# lp_breadboard.net
KiCad netlist of a schematic drawn in EAGLE
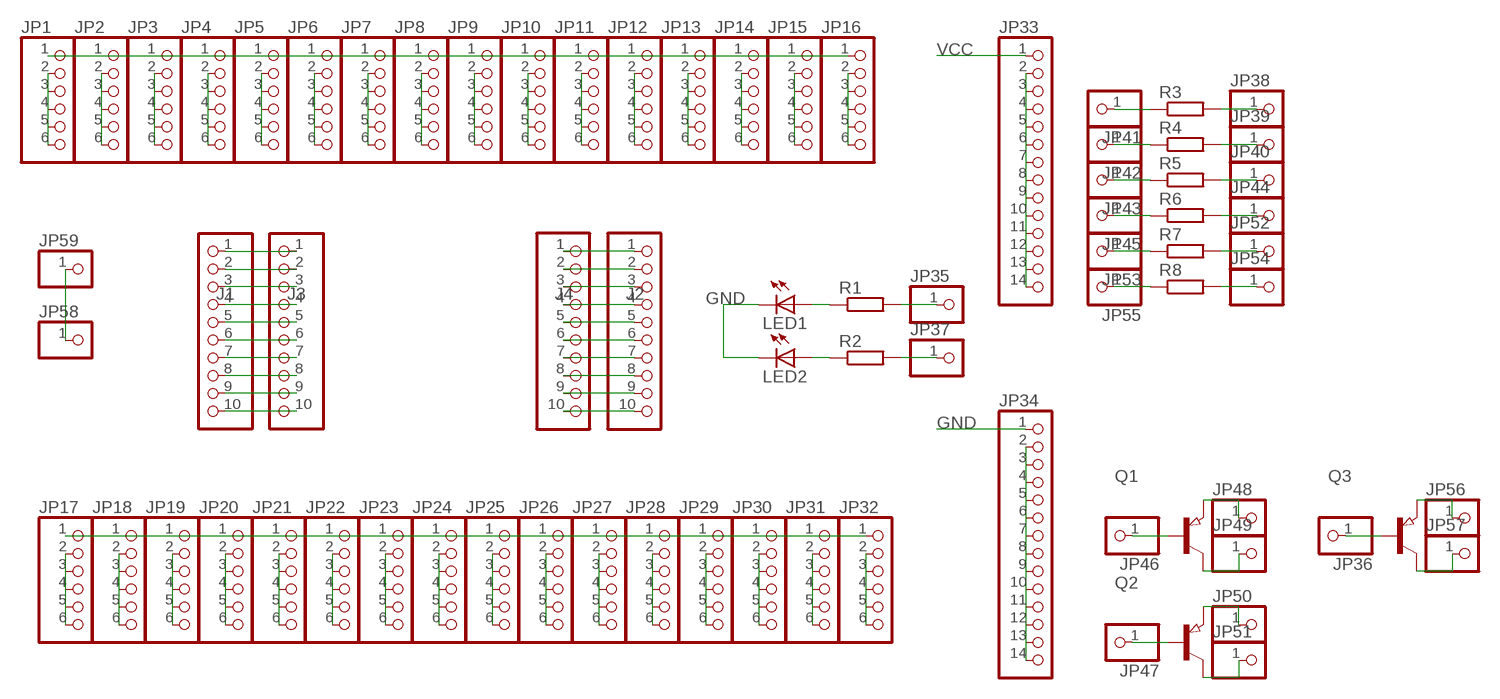
[diagram p0: schematic, sheet 1]

(export (version "E")
  (design (tool "Eeschema 10.0.6"))
  (components
    (comp (ref "J1")
      (value "PINHD-1X10")
      (footprint "eagle-import:1X10")
      (libsource (lib "eagle-import") (part "PINHD-1X10"))
    )
    (comp (ref "J2")
      (value "PINHD-1X10")
      (footprint "eagle-import:1X10")
      (libsource (lib "eagle-import") (part "PINHD-1X10"))
    )
    (comp (ref "J3")
      (value "PINHD-1X10")
      (footprint "eagle-import:1X10")
      (libsource (lib "eagle-import") (part "PINHD-1X10"))
    )
    (comp (ref "J4")
      (value "PINHD-1X10")
      (footprint "eagle-import:1X10")
      (libsource (lib "eagle-import") (part "PINHD-1X10"))
    )
    (comp (ref "JP1")
      (value "PINHD-1X6")
      (footprint "eagle-import:1X06")
      (libsource (lib "eagle-import") (part "PINHD-1X6"))
    )
    (comp (ref "JP2")
      (value "PINHD-1X6")
      (footprint "eagle-import:1X06")
      (libsource (lib "eagle-import") (part "PINHD-1X6"))
    )
    (comp (ref "JP3")
      (value "PINHD-1X6")
      (footprint "eagle-import:1X06")
      (libsource (lib "eagle-import") (part "PINHD-1X6"))
    )
    (comp (ref "JP4")
      (value "PINHD-1X6")
      (footprint "eagle-import:1X06")
      (libsource (lib "eagle-import") (part "PINHD-1X6"))
    )
    (comp (ref "JP5")
      (value "PINHD-1X6")
      (footprint "eagle-import:1X06")
      (libsource (lib "eagle-import") (part "PINHD-1X6"))
    )
    (comp (ref "JP6")
      (value "PINHD-1X6")
      (footprint "eagle-import:1X06")
      (libsource (lib "eagle-import") (part "PINHD-1X6"))
    )
    (comp (ref "JP7")
      (value "PINHD-1X6")
      (footprint "eagle-import:1X06")
      (libsource (lib "eagle-import") (part "PINHD-1X6"))
    )
    (comp (ref "JP8")
      (value "PINHD-1X6")
      (footprint "eagle-import:1X06")
      (libsource (lib "eagle-import") (part "PINHD-1X6"))
    )
    (comp (ref "JP9")
      (value "PINHD-1X6")
      (footprint "eagle-import:1X06")
      (libsource (lib "eagle-import") (part "PINHD-1X6"))
    )
    (comp (ref "JP10")
      (value "PINHD-1X6")
      (footprint "eagle-import:1X06")
      (libsource (lib "eagle-import") (part "PINHD-1X6"))
    )
    (comp (ref "JP11")
      (value "PINHD-1X6")
      (footprint "eagle-import:1X06")
      (libsource (lib "eagle-import") (part "PINHD-1X6"))
    )
    (comp (ref "JP12")
      (value "PINHD-1X6")
      (footprint "eagle-import:1X06")
      (libsource (lib "eagle-import") (part "PINHD-1X6"))
    )
    (comp (ref "JP13")
      (value "PINHD-1X6")
      (footprint "eagle-import:1X06")
      (libsource (lib "eagle-import") (part "PINHD-1X6"))
    )
    (comp (ref "JP14")
      (value "PINHD-1X6")
      (footprint "eagle-import:1X06")
      (libsource (lib "eagle-import") (part "PINHD-1X6"))
    )
    (comp (ref "JP15")
      (value "PINHD-1X6")
      (footprint "eagle-import:1X06")
      (libsource (lib "eagle-import") (part "PINHD-1X6"))
    )
    (comp (ref "JP16")
      (value "PINHD-1X6")
      (footprint "eagle-import:1X06")
      (libsource (lib "eagle-import") (part "PINHD-1X6"))
    )
    (comp (ref "JP17")
      (value "PINHD-1X6")
      (footprint "eagle-import:1X06")
      (libsource (lib "eagle-import") (part "PINHD-1X6"))
    )
    (comp (ref "JP18")
      (value "PINHD-1X6")
      (footprint "eagle-import:1X06")
      (libsource (lib "eagle-import") (part "PINHD-1X6"))
    )
    (comp (ref "JP19")
      (value "PINHD-1X6")
      (footprint "eagle-import:1X06")
      (libsource (lib "eagle-import") (part "PINHD-1X6"))
    )
    (comp (ref "JP20")
      (value "PINHD-1X6")
      (footprint "eagle-import:1X06")
      (libsource (lib "eagle-import") (part "PINHD-1X6"))
    )
    (comp (ref "JP21")
      (value "PINHD-1X6")
      (footprint "eagle-import:1X06")
      (libsource (lib "eagle-import") (part "PINHD-1X6"))
    )
    (comp (ref "JP22")
      (value "PINHD-1X6")
      (footprint "eagle-import:1X06")
      (libsource (lib "eagle-import") (part "PINHD-1X6"))
    )
    (comp (ref "JP23")
      (value "PINHD-1X6")
      (footprint "eagle-import:1X06")
      (libsource (lib "eagle-import") (part "PINHD-1X6"))
    )
    (comp (ref "JP24")
      (value "PINHD-1X6")
      (footprint "eagle-import:1X06")
      (libsource (lib "eagle-import") (part "PINHD-1X6"))
    )
    (comp (ref "JP25")
      (value "PINHD-1X6")
      (footprint "eagle-import:1X06")
      (libsource (lib "eagle-import") (part "PINHD-1X6"))
    )
    (comp (ref "JP26")
      (value "PINHD-1X6")
      (footprint "eagle-import:1X06")
      (libsource (lib "eagle-import") (part "PINHD-1X6"))
    )
    (comp (ref "JP27")
      (value "PINHD-1X6")
      (footprint "eagle-import:1X06")
      (libsource (lib "eagle-import") (part "PINHD-1X6"))
    )
    (comp (ref "JP28")
      (value "PINHD-1X6")
      (footprint "eagle-import:1X06")
      (libsource (lib "eagle-import") (part "PINHD-1X6"))
    )
    (comp (ref "JP29")
      (value "PINHD-1X6")
      (footprint "eagle-import:1X06")
      (libsource (lib "eagle-import") (part "PINHD-1X6"))
    )
    (comp (ref "JP30")
      (value "PINHD-1X6")
      (footprint "eagle-import:1X06")
      (libsource (lib "eagle-import") (part "PINHD-1X6"))
    )
    (comp (ref "JP31")
      (value "PINHD-1X6")
      (footprint "eagle-import:1X06")
      (libsource (lib "eagle-import") (part "PINHD-1X6"))
    )
    (comp (ref "JP32")
      (value "PINHD-1X6")
      (footprint "eagle-import:1X06")
      (libsource (lib "eagle-import") (part "PINHD-1X6"))
    )
    (comp (ref "JP33")
      (value "PINHD-1X14")
      (footprint "eagle-import:1X14")
      (libsource (lib "eagle-import") (part "PINHD-1X14"))
    )
    (comp (ref "JP34")
      (value "PINHD-1X14")
      (footprint "eagle-import:1X14")
      (libsource (lib "eagle-import") (part "PINHD-1X14"))
    )
    (comp (ref "JP35")
      (value "PINHD-1X1")
      (footprint "eagle-import:1X01")
      (libsource (lib "eagle-import") (part "PINHD-1X1"))
    )
    (comp (ref "JP36")
      (value "PINHD-1X1")
      (footprint "eagle-import:1X01")
      (libsource (lib "eagle-import") (part "PINHD-1X1"))
    )
    (comp (ref "JP37")
      (value "PINHD-1X1")
      (footprint "eagle-import:1X01")
      (libsource (lib "eagle-import") (part "PINHD-1X1"))
    )
    (comp (ref "JP38")
      (value "PINHD-1X1")
      (footprint "eagle-import:1X01")
      (libsource (lib "eagle-import") (part "PINHD-1X1"))
    )
    (comp (ref "JP39")
      (value "PINHD-1X1")
      (footprint "eagle-import:1X01")
      (libsource (lib "eagle-import") (part "PINHD-1X1"))
    )
    (comp (ref "JP40")
      (value "PINHD-1X1")
      (footprint "eagle-import:1X01")
      (libsource (lib "eagle-import") (part "PINHD-1X1"))
    )
    (comp (ref "JP41")
      (value "PINHD-1X1")
      (footprint "eagle-import:1X01")
      (libsource (lib "eagle-import") (part "PINHD-1X1"))
    )
    (comp (ref "JP42")
      (value "PINHD-1X1")
      (footprint "eagle-import:1X01")
      (libsource (lib "eagle-import") (part "PINHD-1X1"))
    )
    (comp (ref "JP43")
      (value "PINHD-1X1")
      (footprint "eagle-import:1X01")
      (libsource (lib "eagle-import") (part "PINHD-1X1"))
    )
    (comp (ref "JP44")
      (value "PINHD-1X1")
      (footprint "eagle-import:1X01")
      (libsource (lib "eagle-import") (part "PINHD-1X1"))
    )
    (comp (ref "JP45")
      (value "PINHD-1X1")
      (footprint "eagle-import:1X01")
      (libsource (lib "eagle-import") (part "PINHD-1X1"))
    )
    (comp (ref "JP46")
      (value "PINHD-1X1")
      (footprint "eagle-import:1X01")
      (libsource (lib "eagle-import") (part "PINHD-1X1"))
    )
    (comp (ref "JP47")
      (value "PINHD-1X1")
      (footprint "eagle-import:1X01")
      (libsource (lib "eagle-import") (part "PINHD-1X1"))
    )
    (comp (ref "JP48")
      (value "PINHD-1X1")
      (footprint "eagle-import:1X01")
      (libsource (lib "eagle-import") (part "PINHD-1X1"))
    )
    (comp (ref "JP49")
      (value "PINHD-1X1")
      (footprint "eagle-import:1X01")
      (libsource (lib "eagle-import") (part "PINHD-1X1"))
    )
    (comp (ref "JP50")
      (value "PINHD-1X1")
      (footprint "eagle-import:1X01")
      (libsource (lib "eagle-import") (part "PINHD-1X1"))
    )
    (comp (ref "JP51")
      (value "PINHD-1X1")
      (footprint "eagle-import:1X01")
      (libsource (lib "eagle-import") (part "PINHD-1X1"))
    )
    (comp (ref "JP52")
      (value "PINHD-1X1")
      (footprint "eagle-import:1X01")
      (libsource (lib "eagle-import") (part "PINHD-1X1"))
    )
    (comp (ref "JP53")
      (value "PINHD-1X1")
      (footprint "eagle-import:1X01")
      (libsource (lib "eagle-import") (part "PINHD-1X1"))
    )
    (comp (ref "JP54")
      (value "PINHD-1X1")
      (footprint "eagle-import:1X01")
      (libsource (lib "eagle-import") (part "PINHD-1X1"))
    )
    (comp (ref "JP55")
      (value "PINHD-1X1")
      (footprint "eagle-import:1X01")
      (libsource (lib "eagle-import") (part "PINHD-1X1"))
    )
    (comp (ref "JP56")
      (value "PINHD-1X1")
      (footprint "eagle-import:1X01")
      (libsource (lib "eagle-import") (part "PINHD-1X1"))
    )
    (comp (ref "JP57")
      (value "PINHD-1X1")
      (footprint "eagle-import:1X01")
      (libsource (lib "eagle-import") (part "PINHD-1X1"))
    )
    (comp (ref "JP58")
      (value "PINHD-1X1")
      (footprint "eagle-import:1X01")
      (libsource (lib "eagle-import") (part "PINHD-1X1"))
    )
    (comp (ref "JP59")
      (value "PINHD-1X1")
      (footprint "eagle-import:1X01")
      (libsource (lib "eagle-import") (part "PINHD-1X1"))
    )
    (comp (ref "LED1")
      (value "LEDCHIPLED_1206")
      (footprint "eagle-import:CHIPLED_1206")
      (libsource (lib "eagle-import") (part "LEDCHIPLED_1206"))
    )
    (comp (ref "LED2")
      (value "LEDCHIPLED_1206")
      (footprint "eagle-import:CHIPLED_1206")
      (libsource (lib "eagle-import") (part "LEDCHIPLED_1206"))
    )
    (comp (ref "Q1")
      (value "PNP-TRANSISTOR_SOT23")
      (footprint "eagle-import:SOT23")
      (libsource (lib "eagle-import") (part "PNP-TRANSISTOR_SOT23"))
    )
    (comp (ref "Q2")
      (value "PNP-TRANSISTOR_SOT23")
      (footprint "eagle-import:SOT23")
      (libsource (lib "eagle-import") (part "PNP-TRANSISTOR_SOT23"))
    )
    (comp (ref "Q3")
      (value "PNP-TRANSISTOR_SOT23")
      (footprint "eagle-import:SOT23")
      (libsource (lib "eagle-import") (part "PNP-TRANSISTOR_SOT23"))
    )
    (comp (ref "R1")
      (value "R-EU_R0805")
      (footprint "eagle-import:R0805")
      (libsource (lib "eagle-import") (part "R-EU_R0805"))
    )
    (comp (ref "R2")
      (value "R-EU_R0805")
      (footprint "eagle-import:R0805")
      (libsource (lib "eagle-import") (part "R-EU_R0805"))
    )
    (comp (ref "R3")
      (value "R-EU_R0805")
      (footprint "eagle-import:R0805")
      (libsource (lib "eagle-import") (part "R-EU_R0805"))
    )
    (comp (ref "R4")
      (value "R-EU_R0805")
      (footprint "eagle-import:R0805")
      (libsource (lib "eagle-import") (part "R-EU_R0805"))
    )
    (comp (ref "R5")
      (value "R-EU_R0805")
      (footprint "eagle-import:R0805")
      (libsource (lib "eagle-import") (part "R-EU_R0805"))
    )
    (comp (ref "R6")
      (value "R-EU_R0805")
      (footprint "eagle-import:R0805")
      (libsource (lib "eagle-import") (part "R-EU_R0805"))
    )
    (comp (ref "R7")
      (value "R-EU_R0805")
      (footprint "eagle-import:R0805")
      (libsource (lib "eagle-import") (part "R-EU_R0805"))
    )
    (comp (ref "R8")
      (value "R-EU_R0805")
      (footprint "eagle-import:R0805")
      (libsource (lib "eagle-import") (part "R-EU_R0805"))
    )
  )
  (nets
    (net (code "1") (name "/GND") (class "Default")
      (node (ref "J2") (pin "1") (pinfunction "1_1") (pintype "passive"))
      (node (ref "J4") (pin "1") (pinfunction "1_1") (pintype "passive"))
      (node (ref "JP1") (pin "1") (pinfunction "1_1") (pintype "passive"))
      (node (ref "JP10") (pin "1") (pinfunction "1_1") (pintype "passive"))
      (node (ref "JP11") (pin "1") (pinfunction "1_1") (pintype "passive"))
      (node (ref "JP12") (pin "1") (pinfunction "1_1") (pintype "passive"))
      (node (ref "JP13") (pin "1") (pinfunction "1_1") (pintype "passive"))
      (node (ref "JP14") (pin "1") (pinfunction "1_1") (pintype "passive"))
      (node (ref "JP15") (pin "1") (pinfunction "1_1") (pintype "passive"))
      (node (ref "JP16") (pin "1") (pinfunction "1_1") (pintype "passive"))
      (node (ref "JP2") (pin "1") (pinfunction "1_1") (pintype "passive"))
      (node (ref "JP3") (pin "1") (pinfunction "1_1") (pintype "passive"))
      (node (ref "JP34") (pin "1") (pinfunction "1_1") (pintype "passive"))
      (node (ref "JP4") (pin "1") (pinfunction "1_1") (pintype "passive"))
      (node (ref "JP5") (pin "1") (pinfunction "1_1") (pintype "passive"))
      (node (ref "JP58") (pin "1") (pinfunction "1_1") (pintype "passive"))
      (node (ref "JP59") (pin "1") (pinfunction "1_1") (pintype "passive"))
      (node (ref "JP6") (pin "1") (pinfunction "1_1") (pintype "passive"))
      (node (ref "JP7") (pin "1") (pinfunction "1_1") (pintype "passive"))
      (node (ref "JP8") (pin "1") (pinfunction "1_1") (pintype "passive"))
      (node (ref "JP9") (pin "1") (pinfunction "1_1") (pintype "passive"))
      (node (ref "LED1") (pin "C") (pinfunction "C_C") (pintype "passive"))
      (node (ref "LED2") (pin "C") (pinfunction "C_C") (pintype "passive"))
    )
    (net (code "2") (name "/VCC") (class "Default")
      (node (ref "J1") (pin "1") (pinfunction "1_1") (pintype "passive"))
      (node (ref "J3") (pin "1") (pinfunction "1_1") (pintype "passive"))
      (node (ref "JP17") (pin "1") (pinfunction "1_1") (pintype "passive"))
      (node (ref "JP18") (pin "1") (pinfunction "1_1") (pintype "passive"))
      (node (ref "JP19") (pin "1") (pinfunction "1_1") (pintype "passive"))
      (node (ref "JP20") (pin "1") (pinfunction "1_1") (pintype "passive"))
      (node (ref "JP21") (pin "1") (pinfunction "1_1") (pintype "passive"))
      (node (ref "JP22") (pin "1") (pinfunction "1_1") (pintype "passive"))
      (node (ref "JP23") (pin "1") (pinfunction "1_1") (pintype "passive"))
      (node (ref "JP24") (pin "1") (pinfunction "1_1") (pintype "passive"))
      (node (ref "JP25") (pin "1") (pinfunction "1_1") (pintype "passive"))
      (node (ref "JP26") (pin "1") (pinfunction "1_1") (pintype "passive"))
      (node (ref "JP27") (pin "1") (pinfunction "1_1") (pintype "passive"))
      (node (ref "JP28") (pin "1") (pinfunction "1_1") (pintype "passive"))
      (node (ref "JP29") (pin "1") (pinfunction "1_1") (pintype "passive"))
      (node (ref "JP30") (pin "1") (pinfunction "1_1") (pintype "passive"))
      (node (ref "JP31") (pin "1") (pinfunction "1_1") (pintype "passive"))
      (node (ref "JP32") (pin "1") (pinfunction "1_1") (pintype "passive"))
      (node (ref "JP33") (pin "1") (pinfunction "1_1") (pintype "passive"))
    )
    (net (code "3") (name "Net-(J1-Pad2)") (class "Default")
      (node (ref "J1") (pin "2") (pinfunction "2_2") (pintype "passive"))
      (node (ref "J3") (pin "2") (pinfunction "2_2") (pintype "passive"))
    )
    (net (code "4") (name "Net-(J1-Pad3)") (class "Default")
      (node (ref "J1") (pin "3") (pinfunction "3_3") (pintype "passive"))
      (node (ref "J3") (pin "3") (pinfunction "3_3") (pintype "passive"))
    )
    (net (code "5") (name "Net-(J1-Pad4)") (class "Default")
      (node (ref "J1") (pin "4") (pinfunction "4_4") (pintype "passive"))
      (node (ref "J3") (pin "4") (pinfunction "4_4") (pintype "passive"))
    )
    (net (code "6") (name "Net-(J1-Pad5)") (class "Default")
      (node (ref "J1") (pin "5") (pinfunction "5_5") (pintype "passive"))
      (node (ref "J3") (pin "5") (pinfunction "5_5") (pintype "passive"))
    )
    (net (code "7") (name "Net-(J1-Pad6)") (class "Default")
      (node (ref "J1") (pin "6") (pinfunction "6_6") (pintype "passive"))
      (node (ref "J3") (pin "6") (pinfunction "6_6") (pintype "passive"))
    )
    (net (code "8") (name "Net-(J1-Pad7)") (class "Default")
      (node (ref "J1") (pin "7") (pinfunction "7_7") (pintype "passive"))
      (node (ref "J3") (pin "7") (pinfunction "7_7") (pintype "passive"))
    )
    (net (code "9") (name "Net-(J1-Pad8)") (class "Default")
      (node (ref "J1") (pin "8") (pinfunction "8_8") (pintype "passive"))
      (node (ref "J3") (pin "8") (pinfunction "8_8") (pintype "passive"))
    )
    (net (code "10") (name "Net-(J1-Pad9)") (class "Default")
      (node (ref "J1") (pin "9") (pinfunction "9_9") (pintype "passive"))
      (node (ref "J3") (pin "9") (pinfunction "9_9") (pintype "passive"))
    )
    (net (code "11") (name "Net-(J1-Pad10)") (class "Default")
      (node (ref "J1") (pin "10") (pinfunction "10_10") (pintype "passive"))
      (node (ref "J3") (pin "10") (pinfunction "10_10") (pintype "passive"))
    )
    (net (code "12") (name "Net-(J2-Pad2)") (class "Default")
      (node (ref "J2") (pin "2") (pinfunction "2_2") (pintype "passive"))
      (node (ref "J4") (pin "2") (pinfunction "2_2") (pintype "passive"))
    )
    (net (code "13") (name "Net-(J2-Pad3)") (class "Default")
      (node (ref "J2") (pin "3") (pinfunction "3_3") (pintype "passive"))
      (node (ref "J4") (pin "3") (pinfunction "3_3") (pintype "passive"))
    )
    (net (code "14") (name "Net-(J2-Pad4)") (class "Default")
      (node (ref "J2") (pin "4") (pinfunction "4_4") (pintype "passive"))
      (node (ref "J4") (pin "4") (pinfunction "4_4") (pintype "passive"))
    )
    (net (code "15") (name "Net-(J2-Pad5)") (class "Default")
      (node (ref "J2") (pin "5") (pinfunction "5_5") (pintype "passive"))
      (node (ref "J4") (pin "5") (pinfunction "5_5") (pintype "passive"))
    )
    (net (code "16") (name "Net-(J2-Pad6)") (class "Default")
      (node (ref "J2") (pin "6") (pinfunction "6_6") (pintype "passive"))
      (node (ref "J4") (pin "6") (pinfunction "6_6") (pintype "passive"))
    )
    (net (code "17") (name "Net-(J2-Pad7)") (class "Default")
      (node (ref "J2") (pin "7") (pinfunction "7_7") (pintype "passive"))
      (node (ref "J4") (pin "7") (pinfunction "7_7") (pintype "passive"))
    )
    (net (code "18") (name "Net-(J2-Pad8)") (class "Default")
      (node (ref "J2") (pin "8") (pinfunction "8_8") (pintype "passive"))
      (node (ref "J4") (pin "8") (pinfunction "8_8") (pintype "passive"))
    )
    (net (code "19") (name "Net-(J2-Pad9)") (class "Default")
      (node (ref "J2") (pin "9") (pinfunction "9_9") (pintype "passive"))
      (node (ref "J4") (pin "9") (pinfunction "9_9") (pintype "passive"))
    )
    (net (code "20") (name "Net-(J2-Pad10)") (class "Default")
      (node (ref "J2") (pin "10") (pinfunction "10_10") (pintype "passive"))
      (node (ref "J4") (pin "10") (pinfunction "10_10") (pintype "passive"))
    )
    (net (code "21") (name "Net-(JP1-Pad2)") (class "Default")
      (node (ref "JP1") (pin "2") (pinfunction "2_2") (pintype "passive"))
      (node (ref "JP1") (pin "3") (pinfunction "3_3") (pintype "passive"))
      (node (ref "JP1") (pin "4") (pinfunction "4_4") (pintype "passive"))
      (node (ref "JP1") (pin "5") (pinfunction "5_5") (pintype "passive"))
      (node (ref "JP1") (pin "6") (pinfunction "6_6") (pintype "passive"))
    )
    (net (code "22") (name "Net-(JP2-Pad2)") (class "Default")
      (node (ref "JP2") (pin "2") (pinfunction "2_2") (pintype "passive"))
      (node (ref "JP2") (pin "3") (pinfunction "3_3") (pintype "passive"))
      (node (ref "JP2") (pin "4") (pinfunction "4_4") (pintype "passive"))
      (node (ref "JP2") (pin "5") (pinfunction "5_5") (pintype "passive"))
      (node (ref "JP2") (pin "6") (pinfunction "6_6") (pintype "passive"))
    )
    (net (code "23") (name "Net-(JP3-Pad2)") (class "Default")
      (node (ref "JP3") (pin "2") (pinfunction "2_2") (pintype "passive"))
      (node (ref "JP3") (pin "3") (pinfunction "3_3") (pintype "passive"))
      (node (ref "JP3") (pin "4") (pinfunction "4_4") (pintype "passive"))
      (node (ref "JP3") (pin "5") (pinfunction "5_5") (pintype "passive"))
      (node (ref "JP3") (pin "6") (pinfunction "6_6") (pintype "passive"))
    )
    (net (code "24") (name "Net-(JP4-Pad2)") (class "Default")
      (node (ref "JP4") (pin "2") (pinfunction "2_2") (pintype "passive"))
      (node (ref "JP4") (pin "3") (pinfunction "3_3") (pintype "passive"))
      (node (ref "JP4") (pin "4") (pinfunction "4_4") (pintype "passive"))
      (node (ref "JP4") (pin "5") (pinfunction "5_5") (pintype "passive"))
      (node (ref "JP4") (pin "6") (pinfunction "6_6") (pintype "passive"))
    )
    (net (code "25") (name "Net-(JP5-Pad2)") (class "Default")
      (node (ref "JP5") (pin "2") (pinfunction "2_2") (pintype "passive"))
      (node (ref "JP5") (pin "3") (pinfunction "3_3") (pintype "passive"))
      (node (ref "JP5") (pin "4") (pinfunction "4_4") (pintype "passive"))
      (node (ref "JP5") (pin "5") (pinfunction "5_5") (pintype "passive"))
      (node (ref "JP5") (pin "6") (pinfunction "6_6") (pintype "passive"))
    )
    (net (code "26") (name "Net-(JP6-Pad2)") (class "Default")
      (node (ref "JP6") (pin "2") (pinfunction "2_2") (pintype "passive"))
      (node (ref "JP6") (pin "3") (pinfunction "3_3") (pintype "passive"))
      (node (ref "JP6") (pin "4") (pinfunction "4_4") (pintype "passive"))
      (node (ref "JP6") (pin "5") (pinfunction "5_5") (pintype "passive"))
      (node (ref "JP6") (pin "6") (pinfunction "6_6") (pintype "passive"))
    )
    (net (code "27") (name "Net-(JP7-Pad2)") (class "Default")
      (node (ref "JP7") (pin "2") (pinfunction "2_2") (pintype "passive"))
      (node (ref "JP7") (pin "3") (pinfunction "3_3") (pintype "passive"))
      (node (ref "JP7") (pin "4") (pinfunction "4_4") (pintype "passive"))
      (node (ref "JP7") (pin "5") (pinfunction "5_5") (pintype "passive"))
      (node (ref "JP7") (pin "6") (pinfunction "6_6") (pintype "passive"))
    )
    (net (code "28") (name "Net-(JP8-Pad2)") (class "Default")
      (node (ref "JP8") (pin "2") (pinfunction "2_2") (pintype "passive"))
      (node (ref "JP8") (pin "3") (pinfunction "3_3") (pintype "passive"))
      (node (ref "JP8") (pin "4") (pinfunction "4_4") (pintype "passive"))
      (node (ref "JP8") (pin "5") (pinfunction "5_5") (pintype "passive"))
      (node (ref "JP8") (pin "6") (pinfunction "6_6") (pintype "passive"))
    )
    (net (code "29") (name "Net-(JP9-Pad2)") (class "Default")
      (node (ref "JP9") (pin "2") (pinfunction "2_2") (pintype "passive"))
      (node (ref "JP9") (pin "3") (pinfunction "3_3") (pintype "passive"))
      (node (ref "JP9") (pin "4") (pinfunction "4_4") (pintype "passive"))
      (node (ref "JP9") (pin "5") (pinfunction "5_5") (pintype "passive"))
      (node (ref "JP9") (pin "6") (pinfunction "6_6") (pintype "passive"))
    )
    (net (code "30") (name "Net-(JP10-Pad2)") (class "Default")
      (node (ref "JP10") (pin "2") (pinfunction "2_2") (pintype "passive"))
      (node (ref "JP10") (pin "3") (pinfunction "3_3") (pintype "passive"))
      (node (ref "JP10") (pin "4") (pinfunction "4_4") (pintype "passive"))
      (node (ref "JP10") (pin "5") (pinfunction "5_5") (pintype "passive"))
      (node (ref "JP10") (pin "6") (pinfunction "6_6") (pintype "passive"))
    )
    (net (code "31") (name "Net-(JP11-Pad2)") (class "Default")
      (node (ref "JP11") (pin "2") (pinfunction "2_2") (pintype "passive"))
      (node (ref "JP11") (pin "3") (pinfunction "3_3") (pintype "passive"))
      (node (ref "JP11") (pin "4") (pinfunction "4_4") (pintype "passive"))
      (node (ref "JP11") (pin "5") (pinfunction "5_5") (pintype "passive"))
      (node (ref "JP11") (pin "6") (pinfunction "6_6") (pintype "passive"))
    )
    (net (code "32") (name "Net-(JP12-Pad2)") (class "Default")
      (node (ref "JP12") (pin "2") (pinfunction "2_2") (pintype "passive"))
      (node (ref "JP12") (pin "3") (pinfunction "3_3") (pintype "passive"))
      (node (ref "JP12") (pin "4") (pinfunction "4_4") (pintype "passive"))
      (node (ref "JP12") (pin "5") (pinfunction "5_5") (pintype "passive"))
      (node (ref "JP12") (pin "6") (pinfunction "6_6") (pintype "passive"))
    )
    (net (code "33") (name "Net-(JP13-Pad2)") (class "Default")
      (node (ref "JP13") (pin "2") (pinfunction "2_2") (pintype "passive"))
      (node (ref "JP13") (pin "3") (pinfunction "3_3") (pintype "passive"))
      (node (ref "JP13") (pin "4") (pinfunction "4_4") (pintype "passive"))
      (node (ref "JP13") (pin "5") (pinfunction "5_5") (pintype "passive"))
      (node (ref "JP13") (pin "6") (pinfunction "6_6") (pintype "passive"))
    )
    (net (code "34") (name "Net-(JP14-Pad2)") (class "Default")
      (node (ref "JP14") (pin "2") (pinfunction "2_2") (pintype "passive"))
      (node (ref "JP14") (pin "3") (pinfunction "3_3") (pintype "passive"))
      (node (ref "JP14") (pin "4") (pinfunction "4_4") (pintype "passive"))
      (node (ref "JP14") (pin "5") (pinfunction "5_5") (pintype "passive"))
      (node (ref "JP14") (pin "6") (pinfunction "6_6") (pintype "passive"))
    )
    (net (code "35") (name "Net-(JP15-Pad2)") (class "Default")
      (node (ref "JP15") (pin "2") (pinfunction "2_2") (pintype "passive"))
      (node (ref "JP15") (pin "3") (pinfunction "3_3") (pintype "passive"))
      (node (ref "JP15") (pin "4") (pinfunction "4_4") (pintype "passive"))
      (node (ref "JP15") (pin "5") (pinfunction "5_5") (pintype "passive"))
      (node (ref "JP15") (pin "6") (pinfunction "6_6") (pintype "passive"))
    )
    (net (code "36") (name "Net-(JP16-Pad2)") (class "Default")
      (node (ref "JP16") (pin "2") (pinfunction "2_2") (pintype "passive"))
      (node (ref "JP16") (pin "3") (pinfunction "3_3") (pintype "passive"))
      (node (ref "JP16") (pin "4") (pinfunction "4_4") (pintype "passive"))
      (node (ref "JP16") (pin "5") (pinfunction "5_5") (pintype "passive"))
      (node (ref "JP16") (pin "6") (pinfunction "6_6") (pintype "passive"))
    )
    (net (code "37") (name "Net-(JP17-Pad2)") (class "Default")
      (node (ref "JP17") (pin "2") (pinfunction "2_2") (pintype "passive"))
      (node (ref "JP17") (pin "3") (pinfunction "3_3") (pintype "passive"))
      (node (ref "JP17") (pin "4") (pinfunction "4_4") (pintype "passive"))
      (node (ref "JP17") (pin "5") (pinfunction "5_5") (pintype "passive"))
      (node (ref "JP17") (pin "6") (pinfunction "6_6") (pintype "passive"))
    )
    (net (code "38") (name "Net-(JP18-Pad2)") (class "Default")
      (node (ref "JP18") (pin "2") (pinfunction "2_2") (pintype "passive"))
      (node (ref "JP18") (pin "3") (pinfunction "3_3") (pintype "passive"))
      (node (ref "JP18") (pin "4") (pinfunction "4_4") (pintype "passive"))
      (node (ref "JP18") (pin "5") (pinfunction "5_5") (pintype "passive"))
      (node (ref "JP18") (pin "6") (pinfunction "6_6") (pintype "passive"))
    )
    (net (code "39") (name "Net-(JP19-Pad2)") (class "Default")
      (node (ref "JP19") (pin "2") (pinfunction "2_2") (pintype "passive"))
      (node (ref "JP19") (pin "3") (pinfunction "3_3") (pintype "passive"))
      (node (ref "JP19") (pin "4") (pinfunction "4_4") (pintype "passive"))
      (node (ref "JP19") (pin "5") (pinfunction "5_5") (pintype "passive"))
      (node (ref "JP19") (pin "6") (pinfunction "6_6") (pintype "passive"))
    )
    (net (code "40") (name "Net-(JP20-Pad2)") (class "Default")
      (node (ref "JP20") (pin "2") (pinfunction "2_2") (pintype "passive"))
      (node (ref "JP20") (pin "3") (pinfunction "3_3") (pintype "passive"))
      (node (ref "JP20") (pin "4") (pinfunction "4_4") (pintype "passive"))
      (node (ref "JP20") (pin "5") (pinfunction "5_5") (pintype "passive"))
      (node (ref "JP20") (pin "6") (pinfunction "6_6") (pintype "passive"))
    )
    (net (code "41") (name "Net-(JP21-Pad2)") (class "Default")
      (node (ref "JP21") (pin "2") (pinfunction "2_2") (pintype "passive"))
      (node (ref "JP21") (pin "3") (pinfunction "3_3") (pintype "passive"))
      (node (ref "JP21") (pin "4") (pinfunction "4_4") (pintype "passive"))
      (node (ref "JP21") (pin "5") (pinfunction "5_5") (pintype "passive"))
      (node (ref "JP21") (pin "6") (pinfunction "6_6") (pintype "passive"))
    )
    (net (code "42") (name "Net-(JP22-Pad2)") (class "Default")
      (node (ref "JP22") (pin "2") (pinfunction "2_2") (pintype "passive"))
      (node (ref "JP22") (pin "3") (pinfunction "3_3") (pintype "passive"))
      (node (ref "JP22") (pin "4") (pinfunction "4_4") (pintype "passive"))
      (node (ref "JP22") (pin "5") (pinfunction "5_5") (pintype "passive"))
      (node (ref "JP22") (pin "6") (pinfunction "6_6") (pintype "passive"))
    )
    (net (code "43") (name "Net-(JP23-Pad2)") (class "Default")
      (node (ref "JP23") (pin "2") (pinfunction "2_2") (pintype "passive"))
      (node (ref "JP23") (pin "3") (pinfunction "3_3") (pintype "passive"))
      (node (ref "JP23") (pin "4") (pinfunction "4_4") (pintype "passive"))
      (node (ref "JP23") (pin "5") (pinfunction "5_5") (pintype "passive"))
      (node (ref "JP23") (pin "6") (pinfunction "6_6") (pintype "passive"))
    )
    (net (code "44") (name "Net-(JP24-Pad2)") (class "Default")
      (node (ref "JP24") (pin "2") (pinfunction "2_2") (pintype "passive"))
      (node (ref "JP24") (pin "3") (pinfunction "3_3") (pintype "passive"))
      (node (ref "JP24") (pin "4") (pinfunction "4_4") (pintype "passive"))
      (node (ref "JP24") (pin "5") (pinfunction "5_5") (pintype "passive"))
      (node (ref "JP24") (pin "6") (pinfunction "6_6") (pintype "passive"))
    )
    (net (code "45") (name "Net-(JP25-Pad2)") (class "Default")
      (node (ref "JP25") (pin "2") (pinfunction "2_2") (pintype "passive"))
      (node (ref "JP25") (pin "3") (pinfunction "3_3") (pintype "passive"))
      (node (ref "JP25") (pin "4") (pinfunction "4_4") (pintype "passive"))
      (node (ref "JP25") (pin "5") (pinfunction "5_5") (pintype "passive"))
      (node (ref "JP25") (pin "6") (pinfunction "6_6") (pintype "passive"))
    )
    (net (code "46") (name "Net-(JP26-Pad2)") (class "Default")
      (node (ref "JP26") (pin "2") (pinfunction "2_2") (pintype "passive"))
      (node (ref "JP26") (pin "3") (pinfunction "3_3") (pintype "passive"))
      (node (ref "JP26") (pin "4") (pinfunction "4_4") (pintype "passive"))
      (node (ref "JP26") (pin "5") (pinfunction "5_5") (pintype "passive"))
      (node (ref "JP26") (pin "6") (pinfunction "6_6") (pintype "passive"))
    )
    (net (code "47") (name "Net-(JP27-Pad2)") (class "Default")
      (node (ref "JP27") (pin "2") (pinfunction "2_2") (pintype "passive"))
      (node (ref "JP27") (pin "3") (pinfunction "3_3") (pintype "passive"))
      (node (ref "JP27") (pin "4") (pinfunction "4_4") (pintype "passive"))
      (node (ref "JP27") (pin "5") (pinfunction "5_5") (pintype "passive"))
      (node (ref "JP27") (pin "6") (pinfunction "6_6") (pintype "passive"))
    )
    (net (code "48") (name "Net-(JP28-Pad2)") (class "Default")
      (node (ref "JP28") (pin "2") (pinfunction "2_2") (pintype "passive"))
      (node (ref "JP28") (pin "3") (pinfunction "3_3") (pintype "passive"))
      (node (ref "JP28") (pin "4") (pinfunction "4_4") (pintype "passive"))
      (node (ref "JP28") (pin "5") (pinfunction "5_5") (pintype "passive"))
      (node (ref "JP28") (pin "6") (pinfunction "6_6") (pintype "passive"))
    )
    (net (code "49") (name "Net-(JP29-Pad2)") (class "Default")
      (node (ref "JP29") (pin "2") (pinfunction "2_2") (pintype "passive"))
      (node (ref "JP29") (pin "3") (pinfunction "3_3") (pintype "passive"))
      (node (ref "JP29") (pin "4") (pinfunction "4_4") (pintype "passive"))
      (node (ref "JP29") (pin "5") (pinfunction "5_5") (pintype "passive"))
      (node (ref "JP29") (pin "6") (pinfunction "6_6") (pintype "passive"))
    )
    (net (code "50") (name "Net-(JP30-Pad2)") (class "Default")
      (node (ref "JP30") (pin "2") (pinfunction "2_2") (pintype "passive"))
      (node (ref "JP30") (pin "3") (pinfunction "3_3") (pintype "passive"))
      (node (ref "JP30") (pin "4") (pinfunction "4_4") (pintype "passive"))
      (node (ref "JP30") (pin "5") (pinfunction "5_5") (pintype "passive"))
      (node (ref "JP30") (pin "6") (pinfunction "6_6") (pintype "passive"))
    )
    (net (code "51") (name "Net-(JP31-Pad2)") (class "Default")
      (node (ref "JP31") (pin "2") (pinfunction "2_2") (pintype "passive"))
      (node (ref "JP31") (pin "3") (pinfunction "3_3") (pintype "passive"))
      (node (ref "JP31") (pin "4") (pinfunction "4_4") (pintype "passive"))
      (node (ref "JP31") (pin "5") (pinfunction "5_5") (pintype "passive"))
      (node (ref "JP31") (pin "6") (pinfunction "6_6") (pintype "passive"))
    )
    (net (code "52") (name "Net-(JP32-Pad2)") (class "Default")
      (node (ref "JP32") (pin "2") (pinfunction "2_2") (pintype "passive"))
      (node (ref "JP32") (pin "3") (pinfunction "3_3") (pintype "passive"))
      (node (ref "JP32") (pin "4") (pinfunction "4_4") (pintype "passive"))
      (node (ref "JP32") (pin "5") (pinfunction "5_5") (pintype "passive"))
      (node (ref "JP32") (pin "6") (pinfunction "6_6") (pintype "passive"))
    )
    (net (code "53") (name "Net-(JP33-Pad10)") (class "Default")
      (node (ref "JP33") (pin "10") (pinfunction "10_10") (pintype "passive"))
      (node (ref "JP33") (pin "11") (pinfunction "11_11") (pintype "passive"))
      (node (ref "JP33") (pin "12") (pinfunction "12_12") (pintype "passive"))
      (node (ref "JP33") (pin "13") (pinfunction "13_13") (pintype "passive"))
      (node (ref "JP33") (pin "14") (pinfunction "14_14") (pintype "passive"))
      (node (ref "JP33") (pin "2") (pinfunction "2_2") (pintype "passive"))
      (node (ref "JP33") (pin "3") (pinfunction "3_3") (pintype "passive"))
      (node (ref "JP33") (pin "4") (pinfunction "4_4") (pintype "passive"))
      (node (ref "JP33") (pin "5") (pinfunction "5_5") (pintype "passive"))
      (node (ref "JP33") (pin "6") (pinfunction "6_6") (pintype "passive"))
      (node (ref "JP33") (pin "7") (pinfunction "7_7") (pintype "passive"))
      (node (ref "JP33") (pin "8") (pinfunction "8_8") (pintype "passive"))
      (node (ref "JP33") (pin "9") (pinfunction "9_9") (pintype "passive"))
    )
    (net (code "54") (name "Net-(JP34-Pad10)") (class "Default")
      (node (ref "JP34") (pin "10") (pinfunction "10_10") (pintype "passive"))
      (node (ref "JP34") (pin "11") (pinfunction "11_11") (pintype "passive"))
      (node (ref "JP34") (pin "12") (pinfunction "12_12") (pintype "passive"))
      (node (ref "JP34") (pin "13") (pinfunction "13_13") (pintype "passive"))
      (node (ref "JP34") (pin "14") (pinfunction "14_14") (pintype "passive"))
      (node (ref "JP34") (pin "2") (pinfunction "2_2") (pintype "passive"))
      (node (ref "JP34") (pin "3") (pinfunction "3_3") (pintype "passive"))
      (node (ref "JP34") (pin "4") (pinfunction "4_4") (pintype "passive"))
      (node (ref "JP34") (pin "5") (pinfunction "5_5") (pintype "passive"))
      (node (ref "JP34") (pin "6") (pinfunction "6_6") (pintype "passive"))
      (node (ref "JP34") (pin "7") (pinfunction "7_7") (pintype "passive"))
      (node (ref "JP34") (pin "8") (pinfunction "8_8") (pintype "passive"))
      (node (ref "JP34") (pin "9") (pinfunction "9_9") (pintype "passive"))
    )
    (net (code "55") (name "Net-(JP35-Pad1)") (class "Default")
      (node (ref "JP35") (pin "1") (pinfunction "1_1") (pintype "passive"))
      (node (ref "R1") (pin "2") (pinfunction "2_2") (pintype "passive"))
    )
    (net (code "56") (name "Net-(JP37-Pad1)") (class "Default")
      (node (ref "JP37") (pin "1") (pinfunction "1_1") (pintype "passive"))
      (node (ref "R2") (pin "2") (pinfunction "2_2") (pintype "passive"))
    )
    (net (code "57") (name "Net-(JP38-Pad1)") (class "Default")
      (node (ref "JP38") (pin "1") (pinfunction "1_1") (pintype "passive"))
      (node (ref "R3") (pin "2") (pinfunction "2_2") (pintype "passive"))
    )
    (net (code "58") (name "Net-(JP39-Pad1)") (class "Default")
      (node (ref "JP39") (pin "1") (pinfunction "1_1") (pintype "passive"))
      (node (ref "R4") (pin "2") (pinfunction "2_2") (pintype "passive"))
    )
    (net (code "59") (name "Net-(JP40-Pad1)") (class "Default")
      (node (ref "JP40") (pin "1") (pinfunction "1_1") (pintype "passive"))
      (node (ref "R5") (pin "2") (pinfunction "2_2") (pintype "passive"))
    )
    (net (code "60") (name "Net-(JP41-Pad1)") (class "Default")
      (node (ref "JP41") (pin "1") (pinfunction "1_1") (pintype "passive"))
      (node (ref "R3") (pin "1") (pinfunction "1_1") (pintype "passive"))
    )
    (net (code "61") (name "Net-(JP42-Pad1)") (class "Default")
      (node (ref "JP42") (pin "1") (pinfunction "1_1") (pintype "passive"))
      (node (ref "R4") (pin "1") (pinfunction "1_1") (pintype "passive"))
    )
    (net (code "62") (name "Net-(JP43-Pad1)") (class "Default")
      (node (ref "JP43") (pin "1") (pinfunction "1_1") (pintype "passive"))
      (node (ref "R5") (pin "1") (pinfunction "1_1") (pintype "passive"))
    )
    (net (code "63") (name "Net-(JP44-Pad1)") (class "Default")
      (node (ref "JP44") (pin "1") (pinfunction "1_1") (pintype "passive"))
      (node (ref "R6") (pin "2") (pinfunction "2_2") (pintype "passive"))
    )
    (net (code "64") (name "Net-(JP45-Pad1)") (class "Default")
      (node (ref "JP45") (pin "1") (pinfunction "1_1") (pintype "passive"))
      (node (ref "R6") (pin "1") (pinfunction "1_1") (pintype "passive"))
    )
    (net (code "65") (name "Net-(JP52-Pad1)") (class "Default")
      (node (ref "JP52") (pin "1") (pinfunction "1_1") (pintype "passive"))
      (node (ref "R7") (pin "2") (pinfunction "2_2") (pintype "passive"))
    )
    (net (code "66") (name "Net-(JP53-Pad1)") (class "Default")
      (node (ref "JP53") (pin "1") (pinfunction "1_1") (pintype "passive"))
      (node (ref "R7") (pin "1") (pinfunction "1_1") (pintype "passive"))
    )
    (net (code "67") (name "Net-(JP54-Pad1)") (class "Default")
      (node (ref "JP54") (pin "1") (pinfunction "1_1") (pintype "passive"))
      (node (ref "R8") (pin "2") (pinfunction "2_2") (pintype "passive"))
    )
    (net (code "68") (name "Net-(JP55-Pad1)") (class "Default")
      (node (ref "JP55") (pin "1") (pinfunction "1_1") (pintype "passive"))
      (node (ref "R8") (pin "1") (pinfunction "1_1") (pintype "passive"))
    )
    (net (code "69") (name "Net-(LED1-PadA)") (class "Default")
      (node (ref "LED1") (pin "A") (pinfunction "A_A") (pintype "passive"))
      (node (ref "R1") (pin "1") (pinfunction "1_1") (pintype "passive"))
    )
    (net (code "70") (name "Net-(LED2-PadA)") (class "Default")
      (node (ref "LED2") (pin "A") (pinfunction "A_A") (pintype "passive"))
      (node (ref "R2") (pin "1") (pinfunction "1_1") (pintype "passive"))
    )
    (net (code "71") (name "Net-(Q1-B)") (class "Default")
      (node (ref "JP46") (pin "1") (pinfunction "1_1") (pintype "passive"))
      (node (ref "Q1") (pin "1") (pinfunction "B_1") (pintype "passive"))
    )
    (net (code "72") (name "Net-(Q1-C)") (class "Default")
      (node (ref "JP49") (pin "1") (pinfunction "1_1") (pintype "passive"))
      (node (ref "Q1") (pin "3") (pinfunction "C_3") (pintype "passive"))
    )
    (net (code "73") (name "Net-(Q1-E)") (class "Default")
      (node (ref "JP48") (pin "1") (pinfunction "1_1") (pintype "passive"))
      (node (ref "Q1") (pin "2") (pinfunction "E_2") (pintype "passive"))
    )
    (net (code "74") (name "Net-(Q2-B)") (class "Default")
      (node (ref "JP47") (pin "1") (pinfunction "1_1") (pintype "passive"))
      (node (ref "Q2") (pin "1") (pinfunction "B_1") (pintype "passive"))
    )
    (net (code "75") (name "Net-(Q2-C)") (class "Default")
      (node (ref "JP51") (pin "1") (pinfunction "1_1") (pintype "passive"))
      (node (ref "Q2") (pin "3") (pinfunction "C_3") (pintype "passive"))
    )
    (net (code "76") (name "Net-(Q2-E)") (class "Default")
      (node (ref "JP50") (pin "1") (pinfunction "1_1") (pintype "passive"))
      (node (ref "Q2") (pin "2") (pinfunction "E_2") (pintype "passive"))
    )
    (net (code "77") (name "Net-(Q3-B)") (class "Default")
      (node (ref "JP36") (pin "1") (pinfunction "1_1") (pintype "passive"))
      (node (ref "Q3") (pin "1") (pinfunction "B_1") (pintype "passive"))
    )
    (net (code "78") (name "Net-(Q3-C)") (class "Default")
      (node (ref "JP57") (pin "1") (pinfunction "1_1") (pintype "passive"))
      (node (ref "Q3") (pin "3") (pinfunction "C_3") (pintype "passive"))
    )
    (net (code "79") (name "Net-(Q3-E)") (class "Default")
      (node (ref "JP56") (pin "1") (pinfunction "1_1") (pintype "passive"))
      (node (ref "Q3") (pin "2") (pinfunction "E_2") (pintype "passive"))
    )
  )
)
